# Power_supply.net
KiCad netlist of a schematic drawn in Altium Designer
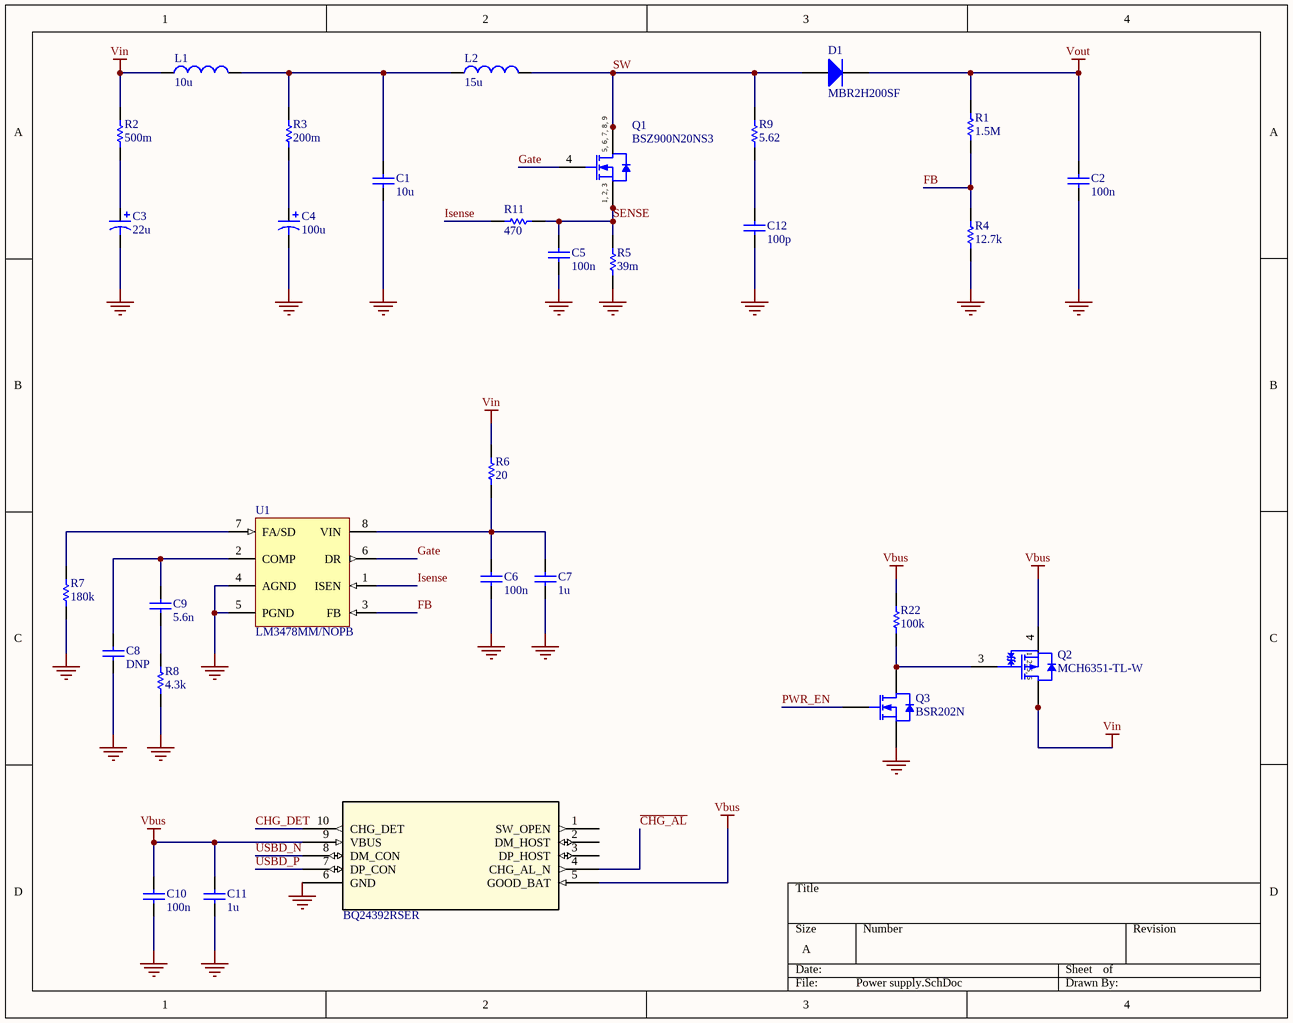
[diagram p0: Power supply.SchDoc]

(export (version "E")
  (design (tool "Eeschema 10.0.6"))
  (components
    (comp (ref "C1")
      (value "10u")
      (footprint "CAPC1206(3216)190_N")
      (description "CAP CER 10UF 25V X7R 1206")
      (fields
        (field (name "MANUFACTURER") "TDK Corporation")
        (field (name "MANUFACTURER PART NUMBER") "C3216X7R1E106K160AB")
      )
      (libsource (lib "Misc Caps") (part "C3216X7R1E106K160AB"))
    )
    (comp (ref "C2")
      (value "100n")
      (footprint "CAPC1812(4532)230_N")
      (fields
        (field (name "MANUFACTURER") "KEMET")
        (field (name "MANUFACTURER PART NUMBER") "C1812C104J2GACAUTO")
        (field (name "TOLERANCE") "5%")
      )
      (libsource (lib "Misc Caps") (part "C1812C104J2GACAUTO"))
    )
    (comp (ref "C3")
      (value "22u")
      (footprint "KEMET A")
      (description "CAP TANT POLY 22UF 6.3V 1206")
      (libsource (lib "Misc Caps") (part "T520A226M006ATE100"))
    )
    (comp (ref "C4")
      (value "100u")
      (footprint "KEMET A")
      (description "POLY TA SMD 3216 100UF 6.3V 20%")
      (libsource (lib "Misc Caps") (part "T520A107M006ATE045"))
    )
    (comp (ref "C5")
      (value "100n")
      (footprint "CAPC0603(1608)100_N")
      (description "CAP CER 0.1UF 10V X7R 0603")
      (fields
        (field (name "MANUFACTURER") "KEMET")
        (field (name "MANUFACTURER PART NUMBER") "C0603C104K8RACTU")
      )
      (libsource (lib "0603 Caps") (part "C0603C104K8RACTU"))
    )
    (comp (ref "C6")
      (value "100n")
      (footprint "CAPC0402(1005)33_N")
      (description "CAP CER 0.1UF 25V X7R 0402")
      (fields
        (field (name "MANUFACTURER") "Yageo")
        (field (name "MANUFACTURER PART NUMBER") "CC0402KRX7R8BB104")
      )
      (libsource (lib "0402 Caps") (part "CC0402KRX7R8BB104"))
    )
    (comp (ref "C7")
      (value "1u")
      (footprint "CAPC0402(1005)33_N")
      (description "CAP CER 1UF 25V X5R 0402")
      (libsource (lib "0402 Caps") (part "CGB2A1X5R1E105K033BC"))
    )
    (comp (ref "C8")
      (value "DNP")
      (footprint "CAPC0603(1608)100_N")
      (libsource (lib "0402 Caps") (part "0402 DNP JUMPER"))
    )
    (comp (ref "C9")
      (value "5.6n")
      (footprint "CAPC0603(1608)100_N")
      (description "Multilayer Ceramic Capacitors MLCC - SMD/SMT 0603 5,600pF 50volts C0G +/-5%")
      (fields
        (field (name "MANUFACTURER") "Murata")
        (field (name "MANUFACTURER PART NUMBER") "GRM1885C1H562JA01D")
      )
      (libsource (lib "0603 Caps") (part "GRM1885C1H562JA01D"))
    )
    (comp (ref "C10")
      (value "100n")
      (footprint "CAPC0402(1005)33_N")
      (description "CAP CER 0.1UF 25V X7R 0402")
      (fields
        (field (name "MANUFACTURER") "Yageo")
        (field (name "MANUFACTURER PART NUMBER") "CC0402KRX7R8BB104")
      )
      (libsource (lib "0402 Caps") (part "CC0402KRX7R8BB104"))
    )
    (comp (ref "C11")
      (value "1u")
      (footprint "CAPC0402(1005)33_N")
      (description "CAP CER 1UF 25V X5R 0402")
      (libsource (lib "0402 Caps") (part "CGB2A1X5R1E105K033BC"))
    )
    (comp (ref "C12")
      (value "100p")
      (footprint "CAPC0603(1608)100_N")
      (description "CAP CER 100PF 250V C0G/NP0 0603")
      (fields
        (field (name "MANUFACTURER") "KEMET")
        (field (name "MANUFACTURER PART NUMBER") "C0603C101JAGACTU")
      )
      (libsource (lib "0603 Caps") (part "C0603C101JAGACTU"))
    )
    (comp (ref "D1")
      (value "MBR2H200SF")
      (footprint "SOD-123FL")
      (description "DIODE SCHOTTKY 200V 2A SOD123")
      (fields
        (field (name "MANUFACTURER") "ON Semiconductor")
        (field (name "MANUFACTURER PART NUMBER") "MBR2H200SFT3G")
      )
      (libsource (lib "Discretes") (part "MBR2H200SF"))
    )
    (comp (ref "L1")
      (value "10u")
      (footprint "VLS6045EX")
      (description "FIXED IND 10UH 3.4A 61 MOHM SMD")
      (libsource (lib "Magnetics") (part "VLS6045EX-100M"))
    )
    (comp (ref "L2")
      (value "15u")
      (footprint "SRU8043")
      (description "FIXED IND 15UH 2.7A 46 MOHM SMD")
      (fields (field (name "MANUFACTURER") "Bourns") (field (name "MANUFACTURER PART NUMBER") "SRU8043-150Y"))
      (libsource (lib "Magnetics") (part "SRU8043-150Y"))
    )
    (comp (ref "Q1")
      (value "BSZ900N20NS3")
      (footprint "PG-TSDSON-8")
      (description "Trans MOSFET N-CH 200V 15.2A 8-Pin TSDSON")
      (fields
        (field (name "MANUFACTURER") "Infineon")
        (field (name "MANUFACTURER PART NUMBER") "BSZ900N20NS3GATMA1")
      )
      (libsource (lib "Discretes") (part "BSZ900N20NS3GATMA1"))
    )
    (comp (ref "Q2")
      (value "MCH6351-TL-W")
      (footprint "SOT23-6P65_210X90L25X32")
      (description "MOSFET PCH 1.8V DRIVE SERIES")
      (fields (field (name "MANUFACTURER") "ON Semiconductor"))
      (libsource (lib "Discretes") (part "MCH6351-TL-W"))
    )
    (comp (ref "Q3")
      (value "BSR202N")
      (footprint "INF-PG-SC59_N")
      (description "Trans MOSFET N-CH 20V 3.8A 3-Pin SC-59 T/R")
      (fields
        (field (name "MANUFACTURER") "Infineon")
        (field (name "MANUFACTURER PART NUMBER") "BSR202NL6327HTSA1")
      )
      (libsource (lib "Discretes") (part "BSR202N"))
    )
    (comp (ref "R1")
      (value "1.5M")
      (footprint "RESC0805(2012)_N")
      (description "RES SMD 1.5M OHM 0.1% 1/10W 0805")
      (fields
        (field (name "MANUFACTURER") "TE Connectivity Passive Product")
        (field (name "MANUFACTURER PART NUMBER") "CPF0805B1M5E1")
      )
      (libsource (lib "0805 Resistors") (part "CPF0805B1M5E1"))
    )
    (comp (ref "R2")
      (value "500m")
      (footprint "RESC0402(1005)_N")
      (description "RES 0.5 OHM 1% 1/16W 0402")
      (fields
        (field (name "MANUFACTURER") "Yageo")
        (field (name "MANUFACTURER PART NUMBER") "RC0402FR-071RL")
      )
      (libsource (lib "0402 Resistors") (part "RL0402FR-070R5L"))
    )
    (comp (ref "R3")
      (value "200m")
      (footprint "RESC0402(1005)_N")
      (description "RES 0.22 OHM 1% 1/16W 0402")
      (fields
        (field (name "MANUFACTURER") "Yageo")
        (field (name "MANUFACTURER PART NUMBER") "RC0402FR-071RL")
      )
      (libsource (lib "0402 Resistors") (part "RL0402FR-070R22L"))
    )
    (comp (ref "R4")
      (value "12.7k")
      (footprint "RESC0805(2012)_N")
      (description "RES SMD 12.7K OHM 0.1% 1/8W 0805")
      (fields
        (field (name "MANUFACTURER") "Yageo")
        (field (name "MANUFACTURER PART NUMBER") "RT0805BRD0712K7L")
      )
      (libsource (lib "0805 Resistors") (part "RT0805BRD0712K7L"))
    )
    (comp (ref "R5")
      (value "39m")
      (footprint "RESC0603(1608)_N")
      (description "RES SMD 0.039 OHM 1% 1/4W 0603")
      (fields (field (name "MANUFACTURER") "Rohm") (field (name "MANUFACTURER PART NUMBER") "UCR03EWPFSR039"))
      (libsource (lib "0603 Resistors") (part "UCR03EWPFSR039"))
    )
    (comp (ref "R6")
      (value "20")
      (footprint "RESC0402(1005)_N")
      (description "RES SMD 20 OHM 1% 1/16W 0402")
      (fields
        (field (name "MANUFACTURER") "Yageo")
        (field (name "MANUFACTURER PART NUMBER") "RC0402FR-0720RL")
      )
      (libsource (lib "0402 Resistors") (part "RC0402FR-0720RL"))
    )
    (comp (ref "R7")
      (value "180k")
      (footprint "RESC0402(1005)_N")
      (description "RES SMD 180K OHM 1% 1/16W 0402")
      (fields
        (field (name "MANUFACTURER") "Yageo")
        (field (name "MANUFACTURER PART NUMBER") "RC0402FR-07180KL")
      )
      (libsource (lib "0402 Resistors") (part "RC0402FR-07180KL"))
    )
    (comp (ref "R8")
      (value "4.3k")
      (footprint "RESC0402(1005)_N")
      (description "RES SMD 4.3K OHM 1% 1/16W 0402")
      (fields
        (field (name "MANUFACTURER") "Yageo")
        (field (name "MANUFACTURER PART NUMBER") "RC0402FR-074K3L")
      )
      (libsource (lib "0402 Resistors") (part "RC0402FR-074K3L"))
    )
    (comp (ref "R9")
      (value "5.62")
      (footprint "RESC0603(1608)_N")
      (description "RES SMD 5.62 OHM 1% 1/10W 0603")
      (fields
        (field (name "MANUFACTURER") "Vishay Dale")
        (field (name "MANUFACTURER PART NUMBER") "CRCW06035R62FKEA")
      )
      (libsource (lib "0603 Resistors") (part "CRCW06035R62FKEA"))
    )
    (comp (ref "R11")
      (value "470")
      (footprint "RESC0402(1005)_N")
      (description "RES SMD 470 OHM 1% 1/16W 0402")
      (fields
        (field (name "MANUFACTURER") "Yageo")
        (field (name "MANUFACTURER PART NUMBER") "RC0402FR-07470RL")
      )
      (libsource (lib "0402 Resistors") (part "RC0402FR-07470RL"))
    )
    (comp (ref "R22")
      (value "100k")
      (footprint "RESC0402(1005)_N")
      (description "RES SMD 100K OHM 1% 1/16W 0402")
      (fields
        (field (name "MANUFACTURER") "Yageo")
        (field (name "MANUFACTURER PART NUMBER") "RC0402FR-07100KL")
      )
      (libsource (lib "0402 Resistors") (part "RC0402FR-07100KL"))
    )
    (comp (ref "U1")
      (value "LM3478MM/NOPB")
      (footprint "DGK0008A_N")
      (description "TEXAS INSTRUMENTS   LM3478MM/NOPB.   N-CHANNEL CONTROLLER, MSOP-8, FULL REEL")
      (fields (field (name "MANUFACTURER") "Texas Instruments"))
      (libsource (lib "IC") (part "LM3478MM/NOPB"))
    )
    (comp (ref "U2")
      (value "BQ24392RSER")
      (footprint "QFN50P200X150X60-10N")
      (description "SPST USB 2.0 High-Speed Switch With Battery Charging Detection")
      (libsource (lib "IC") (part "BQ24392RSER"))
    )
  )
  (nets
    (net (code "1") (name "/CHG_DET") (class "Default")
      (node (ref "U2") (pin "10") (pinfunction "CHG_DET_10") (pintype "output"))
    )
    (net (code "2") (name "/FB") (class "Default")
      (node (ref "R1") (pin "1") (pinfunction "1_1") (pintype "passive"))
      (node (ref "R4") (pin "2") (pinfunction "2_2") (pintype "passive"))
      (node (ref "U1") (pin "3") (pinfunction "FB_3") (pintype "input"))
    )
    (net (code "3") (name "/Gate") (class "Default")
      (node (ref "Q1") (pin "4") (pinfunction "GATE_4") (pintype "passive"))
      (node (ref "U1") (pin "6") (pinfunction "DR_6") (pintype "output"))
    )
    (net (code "4") (name "/Isense") (class "Default")
      (node (ref "R11") (pin "1") (pinfunction "1_1") (pintype "passive"))
      (node (ref "U1") (pin "1") (pinfunction "ISEN_1") (pintype "input"))
    )
    (net (code "5") (name "/PWR_EN") (class "Default")
      (node (ref "Q3") (pin "1") (pinfunction "GATE_1") (pintype "passive"))
    )
    (net (code "6") (name "/SENSE") (class "Default")
      (node (ref "C5") (pin "2") (pinfunction "2_2") (pintype "passive"))
      (node (ref "Q1") (pin "1") (pinfunction "SOURCE_1") (pintype "passive"))
      (node (ref "Q1") (pin "2") (pinfunction "SOURCE_2") (pintype "passive"))
      (node (ref "Q1") (pin "3") (pinfunction "SOURCE_3") (pintype "passive"))
      (node (ref "R11") (pin "2") (pinfunction "2_2") (pintype "passive"))
      (node (ref "R5") (pin "2") (pinfunction "2_2") (pintype "passive"))
    )
    (net (code "7") (name "/SW") (class "Default")
      (node (ref "D1") (pin "1") (pinfunction "A_1") (pintype "passive"))
      (node (ref "L2") (pin "2") (pinfunction "2_2") (pintype "passive"))
      (node (ref "Q1") (pin "5") (pinfunction "DRAIN_5") (pintype "passive"))
      (node (ref "Q1") (pin "6") (pinfunction "DRAIN_6") (pintype "passive"))
      (node (ref "Q1") (pin "7") (pinfunction "DRAIN_7") (pintype "passive"))
      (node (ref "Q1") (pin "8") (pinfunction "DRAIN_8") (pintype "passive"))
      (node (ref "Q1") (pin "9") (pinfunction "DRAIN_9") (pintype "passive"))
      (node (ref "R9") (pin "2") (pinfunction "2_2") (pintype "passive"))
    )
    (net (code "8") (name "/USBD_N") (class "Default")
      (node (ref "U2") (pin "8") (pinfunction "DM_CON_8") (pintype "bidirectional"))
    )
    (net (code "9") (name "/USBD_P") (class "Default")
      (node (ref "U2") (pin "7") (pinfunction "DP_CON_7") (pintype "bidirectional"))
    )
    (net (code "10") (name "/~{CHG_AL}") (class "Default")
      (node (ref "U2") (pin "4") (pinfunction "CHG_AL_N_4") (pintype "output"))
    )
    (net (code "11") (name "GND") (class "Default")
      (node (ref "C1") (pin "1") (pinfunction "1_1") (pintype "passive"))
      (node (ref "C10") (pin "1") (pinfunction "1_1") (pintype "passive"))
      (node (ref "C11") (pin "1") (pinfunction "1_1") (pintype "passive"))
      (node (ref "C12") (pin "1") (pinfunction "1_1") (pintype "passive"))
      (node (ref "C2") (pin "1") (pinfunction "1_1") (pintype "passive"))
      (node (ref "C3") (pin "2") (pinfunction "2_2") (pintype "passive"))
      (node (ref "C4") (pin "2") (pinfunction "2_2") (pintype "passive"))
      (node (ref "C5") (pin "1") (pinfunction "1_1") (pintype "passive"))
      (node (ref "C6") (pin "1") (pinfunction "1_1") (pintype "passive"))
      (node (ref "C7") (pin "1") (pinfunction "1_1") (pintype "passive"))
      (node (ref "C8") (pin "1") (pinfunction "1_1") (pintype "passive"))
      (node (ref "Q3") (pin "2") (pinfunction "SOURCE_2") (pintype "passive"))
      (node (ref "R4") (pin "1") (pinfunction "1_1") (pintype "passive"))
      (node (ref "R5") (pin "1") (pinfunction "1_1") (pintype "passive"))
      (node (ref "R7") (pin "1") (pinfunction "1_1") (pintype "passive"))
      (node (ref "R8") (pin "1") (pinfunction "1_1") (pintype "passive"))
      (node (ref "U1") (pin "4") (pinfunction "AGND_4") (pintype "power_in"))
      (node (ref "U1") (pin "5") (pinfunction "PGND_5") (pintype "power_in"))
      (node (ref "U2") (pin "6") (pinfunction "GND_6") (pintype "power_in"))
    )
    (net (code "12") (name "Net-(C1-Pad2)") (class "Default")
      (node (ref "C1") (pin "2") (pinfunction "2_2") (pintype "passive"))
      (node (ref "L1") (pin "2") (pinfunction "2_2") (pintype "passive"))
      (node (ref "L2") (pin "1") (pinfunction "1_1") (pintype "passive"))
      (node (ref "R3") (pin "2") (pinfunction "2_2") (pintype "passive"))
    )
    (net (code "13") (name "Net-(C3-Pad1)") (class "Default")
      (node (ref "C3") (pin "1") (pinfunction "1_1") (pintype "passive"))
      (node (ref "R2") (pin "1") (pinfunction "1_1") (pintype "passive"))
    )
    (net (code "14") (name "Net-(C4-Pad1)") (class "Default")
      (node (ref "C4") (pin "1") (pinfunction "1_1") (pintype "passive"))
      (node (ref "R3") (pin "1") (pinfunction "1_1") (pintype "passive"))
    )
    (net (code "15") (name "Net-(C9-Pad1)") (class "Default")
      (node (ref "C9") (pin "1") (pinfunction "1_1") (pintype "passive"))
      (node (ref "R8") (pin "2") (pinfunction "2_2") (pintype "passive"))
    )
    (net (code "16") (name "Net-(C12-Pad2)") (class "Default")
      (node (ref "C12") (pin "2") (pinfunction "2_2") (pintype "passive"))
      (node (ref "R9") (pin "1") (pinfunction "1_1") (pintype "passive"))
    )
    (net (code "17") (name "Net-(Q2-G)") (class "Default")
      (node (ref "Q2") (pin "3") (pinfunction "G_3") (pintype "passive"))
      (node (ref "Q3") (pin "3") (pinfunction "DRAIN_3") (pintype "passive"))
      (node (ref "R22") (pin "1") (pinfunction "1_1") (pintype "passive"))
    )
    (net (code "18") (name "Net-(U1-COMP)") (class "Default")
      (node (ref "C8") (pin "2") (pinfunction "2_2") (pintype "passive"))
      (node (ref "C9") (pin "2") (pinfunction "2_2") (pintype "passive"))
      (node (ref "U1") (pin "2") (pinfunction "COMP_2") (pintype "passive"))
    )
    (net (code "19") (name "Net-(U1-FA{slash}SD)") (class "Default")
      (node (ref "R7") (pin "2") (pinfunction "2_2") (pintype "passive"))
      (node (ref "U1") (pin "7") (pinfunction "FA/SD_7") (pintype "input"))
    )
    (net (code "20") (name "Net-(U1-VIN)") (class "Default")
      (node (ref "C6") (pin "2") (pinfunction "2_2") (pintype "passive"))
      (node (ref "C7") (pin "2") (pinfunction "2_2") (pintype "passive"))
      (node (ref "R6") (pin "1") (pinfunction "1_1") (pintype "passive"))
      (node (ref "U1") (pin "8") (pinfunction "VIN_8") (pintype "power_in"))
    )
    (net (code "21") (name "Vbus") (class "Default")
      (node (ref "C10") (pin "2") (pinfunction "2_2") (pintype "passive"))
      (node (ref "C11") (pin "2") (pinfunction "2_2") (pintype "passive"))
      (node (ref "Q2") (pin "4") (pinfunction "S_4") (pintype "passive"))
      (node (ref "R22") (pin "2") (pinfunction "2_2") (pintype "passive"))
      (node (ref "U2") (pin "5") (pinfunction "GOOD_BAT_5") (pintype "input"))
      (node (ref "U2") (pin "9") (pinfunction "VBUS_9") (pintype "input"))
    )
    (net (code "22") (name "Vin") (class "Default")
      (node (ref "L1") (pin "1") (pinfunction "1_1") (pintype "passive"))
      (node (ref "Q2") (pin "1") (pinfunction "D_1") (pintype "passive"))
      (node (ref "Q2") (pin "2") (pinfunction "D_2") (pintype "passive"))
      (node (ref "Q2") (pin "5") (pinfunction "D_5") (pintype "passive"))
      (node (ref "Q2") (pin "6") (pinfunction "D_6") (pintype "passive"))
      (node (ref "R2") (pin "2") (pinfunction "2_2") (pintype "passive"))
      (node (ref "R6") (pin "2") (pinfunction "2_2") (pintype "passive"))
    )
    (net (code "23") (name "Vout") (class "Default")
      (node (ref "C2") (pin "2") (pinfunction "2_2") (pintype "passive"))
      (node (ref "D1") (pin "2") (pinfunction "K_2") (pintype "passive"))
      (node (ref "R1") (pin "2") (pinfunction "2_2") (pintype "passive"))
    )
    (net (code "24") (name "unconnected-(U2-DM_HOST-Pad2)") (class "Default")
      (node (ref "U2") (pin "2") (pinfunction "DM_HOST_2") (pintype "bidirectional"))
    )
    (net (code "25") (name "unconnected-(U2-DP_HOST-Pad3)") (class "Default")
      (node (ref "U2") (pin "3") (pinfunction "DP_HOST_3") (pintype "bidirectional"))
    )
    (net (code "26") (name "unconnected-(U2-SW_OPEN-Pad1)") (class "Default")
      (node (ref "U2") (pin "1") (pinfunction "SW_OPEN_1") (pintype "output"))
    )
  )
)
